# LightStickButton.net
KiCad netlist of a schematic drawn in EAGLE
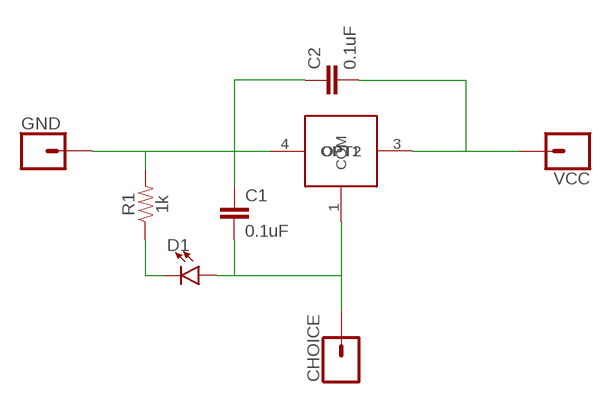
[diagram p0: schematic, sheet 1]

(export (version "E")
  (design (tool "Eeschema 10.0.6"))
  (components
    (comp (ref "B1")
      (value "KS12R22CQD")
      (footprint "eagle-import:KS12R22CQD")
      (libsource (lib "eagle-import") (part "KS12R22CQD"))
    )
    (comp (ref "C1")
      (value "0.1uF")
      (footprint "eagle-import:0603")
      (libsource (lib "eagle-import") (part "0.1UF-0603-25V-5%"))
    )
    (comp (ref "C2")
      (value "0.1uF")
      (footprint "eagle-import:0603")
      (libsource (lib "eagle-import") (part "0.1UF-0603-25V-5%"))
    )
    (comp (ref "CHOICE")
      (value "CONN_01")
      (footprint "eagle-import:1X01")
      (libsource (lib "eagle-import") (part "CONN_01"))
    )
    (comp (ref "D1")
      (value "LED0603")
      (footprint "eagle-import:LED-0603")
      (libsource (lib "eagle-import") (part "LED0603"))
    )
    (comp (ref "GND")
      (value "CONN_01")
      (footprint "eagle-import:1X01")
      (libsource (lib "eagle-import") (part "CONN_01"))
    )
    (comp (ref "R1")
      (value "1k")
      (footprint "eagle-import:0603")
      (libsource (lib "eagle-import") (part "1KOHM-0603-1/10W-1%"))
    )
    (comp (ref "VCC")
      (value "CONN_01")
      (footprint "eagle-import:1X01")
      (libsource (lib "eagle-import") (part "CONN_01"))
    )
  )
  (nets
    (net (code "1") (name "Net-(B1-COM)") (class "Default")
      (node (ref "B1") (pin "1") (pinfunction "COM_1") (pintype "bidirectional"))
      (node (ref "C1") (pin "2") (pinfunction "2_2") (pintype "passive"))
      (node (ref "CHOICE") (pin "1") (pinfunction "1_1") (pintype "passive"))
      (node (ref "D1") (pin "A") (pinfunction "A_A") (pintype "passive"))
    )
    (net (code "2") (name "Net-(B1-OPT1)") (class "Default")
      (node (ref "B1") (pin "3") (pinfunction "OPT1_3") (pintype "bidirectional"))
      (node (ref "C2") (pin "2") (pinfunction "2_2") (pintype "passive"))
      (node (ref "VCC") (pin "1") (pinfunction "1_1") (pintype "passive"))
    )
    (net (code "3") (name "Net-(B1-OPT2)") (class "Default")
      (node (ref "B1") (pin "4") (pinfunction "OPT2_4") (pintype "bidirectional"))
      (node (ref "C1") (pin "1") (pinfunction "1_1") (pintype "passive"))
      (node (ref "C2") (pin "1") (pinfunction "1_1") (pintype "passive"))
      (node (ref "GND") (pin "1") (pinfunction "1_1") (pintype "passive"))
      (node (ref "R1") (pin "2") (pinfunction "2_2") (pintype "passive"))
    )
    (net (code "4") (name "Net-(D1-PadC)") (class "Default")
      (node (ref "D1") (pin "C") (pinfunction "C_C") (pintype "passive"))
      (node (ref "R1") (pin "1") (pinfunction "1_1") (pintype "passive"))
    )
  )
)
